# Micro.net
KiCad netlist of a schematic drawn in Altium Designer
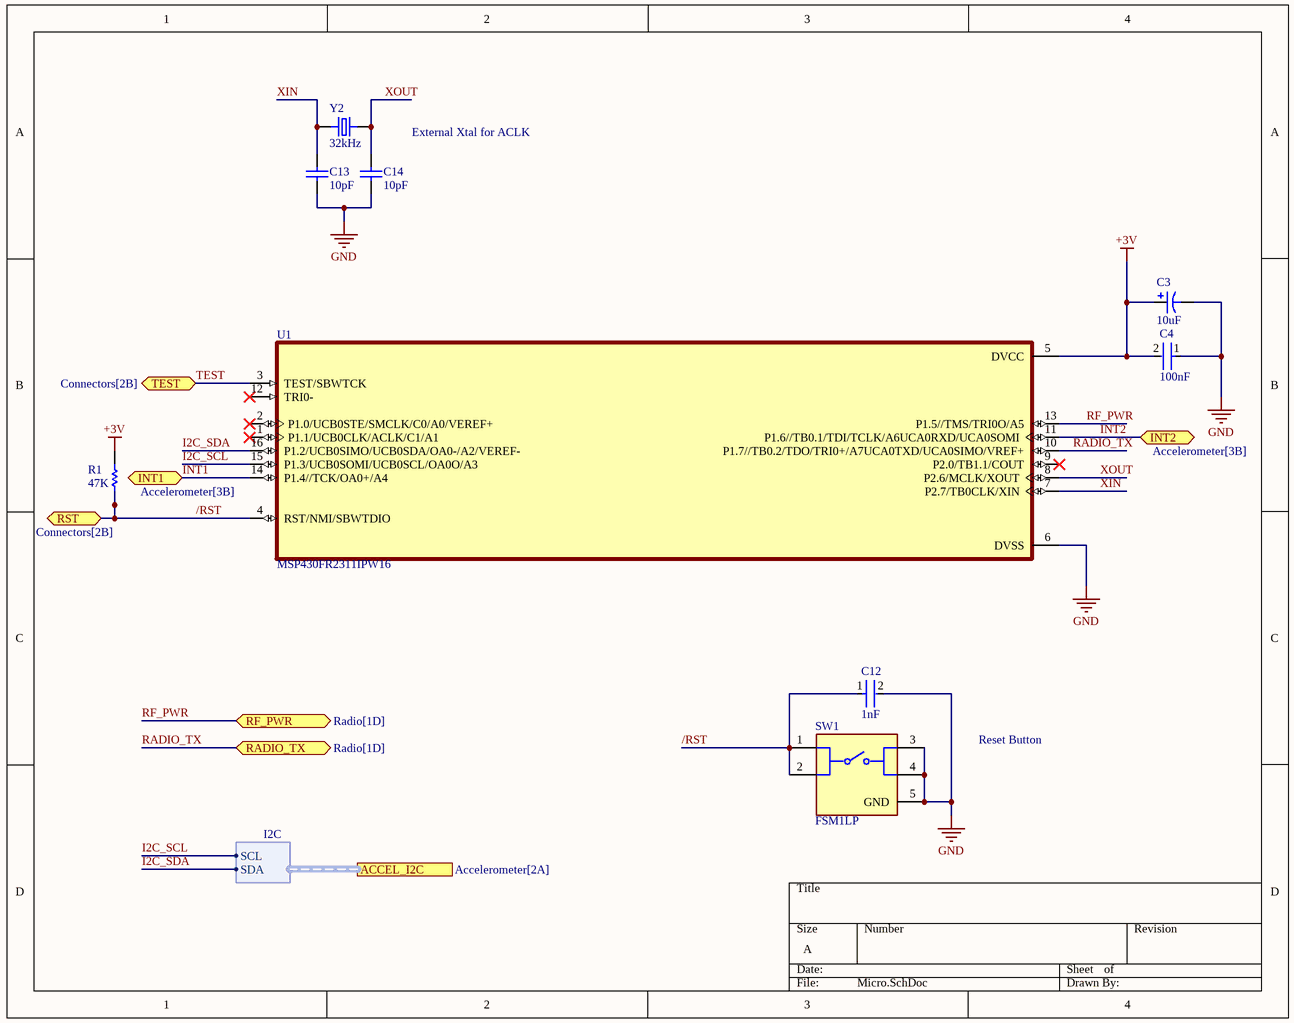
[diagram p0: Micro.SchDoc]

(export (version "E")
  (design (tool "Eeschema 10.0.6"))
  (components
    (comp (ref "C3")
      (value "10uF")
      (footprint "C0805")
      (description "Alum. Electrolytic Cap 10µF 50V; 5mm Surface Mount; Lifetime 2000h; +105°C")
      (fields
        (field (name "MANUFACTURER") "Wurth Electronics")
        (field (name "MANUFACTURER PART NUMBER") "865080642006")
        (field (name "PUBLISHER") "Altium Limited")
      )
      (libsource (lib "Miscellaneous Devices") (part "Cap Pol3"))
    )
    (comp (ref "C4")
      (value "100nF")
      (footprint "FP-C0402-BB-MFG")
      (description "CAP CER 0.1UF 10V X5R 0402")
      (fields (field (name "MANUFACTURER") "Kemet") (field (name "TOLERANCE") "0.1"))
      (libsource (lib "Altium Content Vault") (part "b4654b650e69147ec39a6b967a45e02"))
    )
    (comp (ref "C12")
      (value "1nF")
      (footprint "FP-0603-L_1_6_0_15-W_0_81-IPC_A")
      (description "General Purpose Ceramic Capacitor, 0603, 1nF, 10%, X7R, 15%, 50V")
      (fields (field (name "VOLTAGE") "50V") (field (name "TOLERANCE") "10%"))
      (libsource (lib "Altium Content Vault") (part "02cd4be3c70576c341d710602a673aa"))
    )
    (comp (ref "C13")
      (value "10pF")
      (footprint "CAPC1608X90X40ML10T20")
      (description "Chip Capacitor, 10 pF, +/- 5%, 50 V, -55 to 125 degC, 0603 (1608 Metric), RoHS, Tape and Reel")
      (fields (field (name "VOLTAGE") "50V") (field (name "TOLERANCE") "5%"))
      (libsource (lib "Altium Content Vault") (part "CAP-NP-2"))
    )
    (comp (ref "C14")
      (value "10pF")
      (footprint "CAPC1608X90X40ML10T20")
      (description "Chip Capacitor, 10 pF, +/- 5%, 50 V, -55 to 125 degC, 0603 (1608 Metric), RoHS, Tape and Reel")
      (fields (field (name "VOLTAGE") "50V") (field (name "TOLERANCE") "5%"))
      (libsource (lib "Altium Content Vault") (part "CAP-NP-2"))
    )
    (comp (ref "R1")
      (value "47K")
      (footprint "J1-0603")
      (description "Resistor")
      (fields (field (name "PUBLISHER") "Altium Limited"))
      (libsource (lib "Miscellaneous Devices") (part "Res1"))
    )
    (comp (ref "SW1")
      (value "FSM1LP")
      (footprint "FP-FSM1LP-MFG")
      (description "SWITCH TACTILE SPST-NO 0.05A 24V")
      (libsource (lib "Altium Content Vault") (part "3a9e64be5c1b186b34f28721102267a"))
    )
    (comp (ref "U1")
      (value "MSP430FR2311IPW16")
      (footprint "SOP65P640X120-16N")
      (fields (field (name "MF") "Texas Instruments"))
      (libsource (lib "MSP430FR2311IPW16") (part "MSP430FR2311IPW16"))
    )
    (comp (ref "Y2")
      (value "32kHz")
      (footprint "XTAL_ECS-.327-6-34RR-TR")
      (description "32.768kHz Â±20ppm Crystal 6pF 40 kOhms 2-SMD, No Lead")
      (fields (field (name "MF") "ECS Inc.") (field (name "MP") "ECS-.327-6-34RR-TR"))
      (libsource (lib "SnapEDAsch") (part "ECS-.327-6-34RR-TR"))
    )
  )
  (nets
    (net (code "2") (name "+3V") (class "Default")
      (node (ref "C3") (pin "1") (pinfunction "1_1") (pintype "passive"))
      (node (ref "C4") (pin "2") (pinfunction "2_2") (pintype "passive"))
      (node (ref "R1") (pin "2") (pinfunction "2_2") (pintype "passive"))
      (node (ref "U1") (pin "5") (pinfunction "DVCC_5") (pintype "power_in"))
    )
    (net (code "3") (name "/I2C_SCL") (class "Default")
      (node (ref "U1") (pin "15") (pinfunction "P1.3/UCB0SOMI/UCB0SCL/OA0O/A3_15") (pintype "bidirectional"))
    )
    (net (code "4") (name "/I2C_SDA") (class "Default")
      (node (ref "U1") (pin "16") (pinfunction "P1.2/UCB0SIMO/UCB0SDA/OA0-/A2/VEREF-_16") (pintype "bidirectional"))
    )
    (net (code "5") (name "/INT1") (class "Default")
      (node (ref "U1") (pin "14") (pinfunction "P1.4//TCK/OA0+/A4_14") (pintype "bidirectional"))
    )
    (net (code "6") (name "/INT2") (class "Default")
      (node (ref "U1") (pin "11") (pinfunction "P1.6//TB0.1/TDI/TCLK/A6UCA0RXD/UCA0SOMI_11") (pintype "bidirectional"))
    )
    (net (code "7") (name "/RADIO_TX") (class "Default")
      (node (ref "U1") (pin "10") (pinfunction "P1.7//TB0.2/TDO/TRI0+/A7UCA0TXD/UCA0SIMO/VREF+_10") (pintype "bidirectional"))
    )
    (net (code "8") (name "/RF_PWR") (class "Default")
      (node (ref "U1") (pin "13") (pinfunction "P1.5//TMS/TRI0O/A5_13") (pintype "bidirectional"))
    )
    (net (code "9") (name "/TEST") (class "Default")
      (node (ref "U1") (pin "3") (pinfunction "TEST/SBWTCK_3") (pintype "input"))
    )
    (net (code "10") (name "/XIN") (class "Default")
      (node (ref "C13") (pin "2") (pinfunction "2_2") (pintype "passive"))
      (node (ref "U1") (pin "7") (pinfunction "P2.7/TB0CLK/XIN_7") (pintype "bidirectional"))
      (node (ref "Y2") (pin "1") (pinfunction "I/O_1") (pintype "passive"))
    )
    (net (code "11") (name "/XOUT") (class "Default")
      (node (ref "C14") (pin "2") (pinfunction "2_2") (pintype "passive"))
      (node (ref "U1") (pin "8") (pinfunction "P2.6/MCLK/XOUT_8") (pintype "bidirectional"))
      (node (ref "Y2") (pin "2") (pinfunction "O/I_2") (pintype "passive"))
    )
    (net (code "13") (name "/{slash}RST") (class "Default")
      (node (ref "C12") (pin "1") (pinfunction "1_1") (pintype "passive"))
      (node (ref "R1") (pin "1") (pinfunction "1_1") (pintype "passive"))
      (node (ref "SW1") (pin "1") (pinfunction "1_1") (pintype "passive"))
      (node (ref "SW1") (pin "2") (pinfunction "2_2") (pintype "passive"))
      (node (ref "U1") (pin "4") (pinfunction "RST/NMI/SBWTDIO_4") (pintype "bidirectional"))
    )
    (net (code "14") (name "GND") (class "Default")
      (node (ref "C12") (pin "2") (pinfunction "2_2") (pintype "passive"))
      (node (ref "C13") (pin "1") (pinfunction "1_1") (pintype "passive"))
      (node (ref "C14") (pin "1") (pinfunction "1_1") (pintype "passive"))
      (node (ref "C3") (pin "2") (pinfunction "2_2") (pintype "passive"))
      (node (ref "C4") (pin "1") (pinfunction "1_1") (pintype "passive"))
      (node (ref "SW1") (pin "3") (pinfunction "3_3") (pintype "passive"))
      (node (ref "SW1") (pin "4") (pinfunction "4_4") (pintype "passive"))
      (node (ref "SW1") (pin "5") (pinfunction "GND_5") (pintype "power_in"))
      (node (ref "U1") (pin "6") (pinfunction "DVSS_6") (pintype "power_in"))
    )
    (net (code "15") (name "unconnected-(U1-P1.0{slash}UCB0STE{slash}SMCLK{slash}C0{slash}A0{slash}VEREF+-Pad2)") (class "Default")
      (node (ref "U1") (pin "2") (pinfunction "P1.0/UCB0STE/SMCLK/C0/A0/VEREF+_2") (pintype "bidirectional+no_connect"))
    )
    (net (code "16") (name "unconnected-(U1-P1.1{slash}UCB0CLK{slash}ACLK{slash}C1{slash}A1-Pad1)") (class "Default")
      (node (ref "U1") (pin "1") (pinfunction "P1.1/UCB0CLK/ACLK/C1/A1_1") (pintype "bidirectional+no_connect"))
    )
    (net (code "17") (name "unconnected-(U1-P2.0{slash}TB1.1{slash}COUT-Pad9)") (class "Default")
      (node (ref "U1") (pin "9") (pinfunction "P2.0/TB1.1/COUT_9") (pintype "bidirectional+no_connect"))
    )
    (net (code "18") (name "unconnected-(U1-TRI0--Pad12)") (class "Default")
      (node (ref "U1") (pin "12") (pinfunction "TRI0-_12") (pintype "input+no_connect"))
    )
  )
)
